# Out_conn.net
KiCad netlist of a schematic drawn in Altium Designer
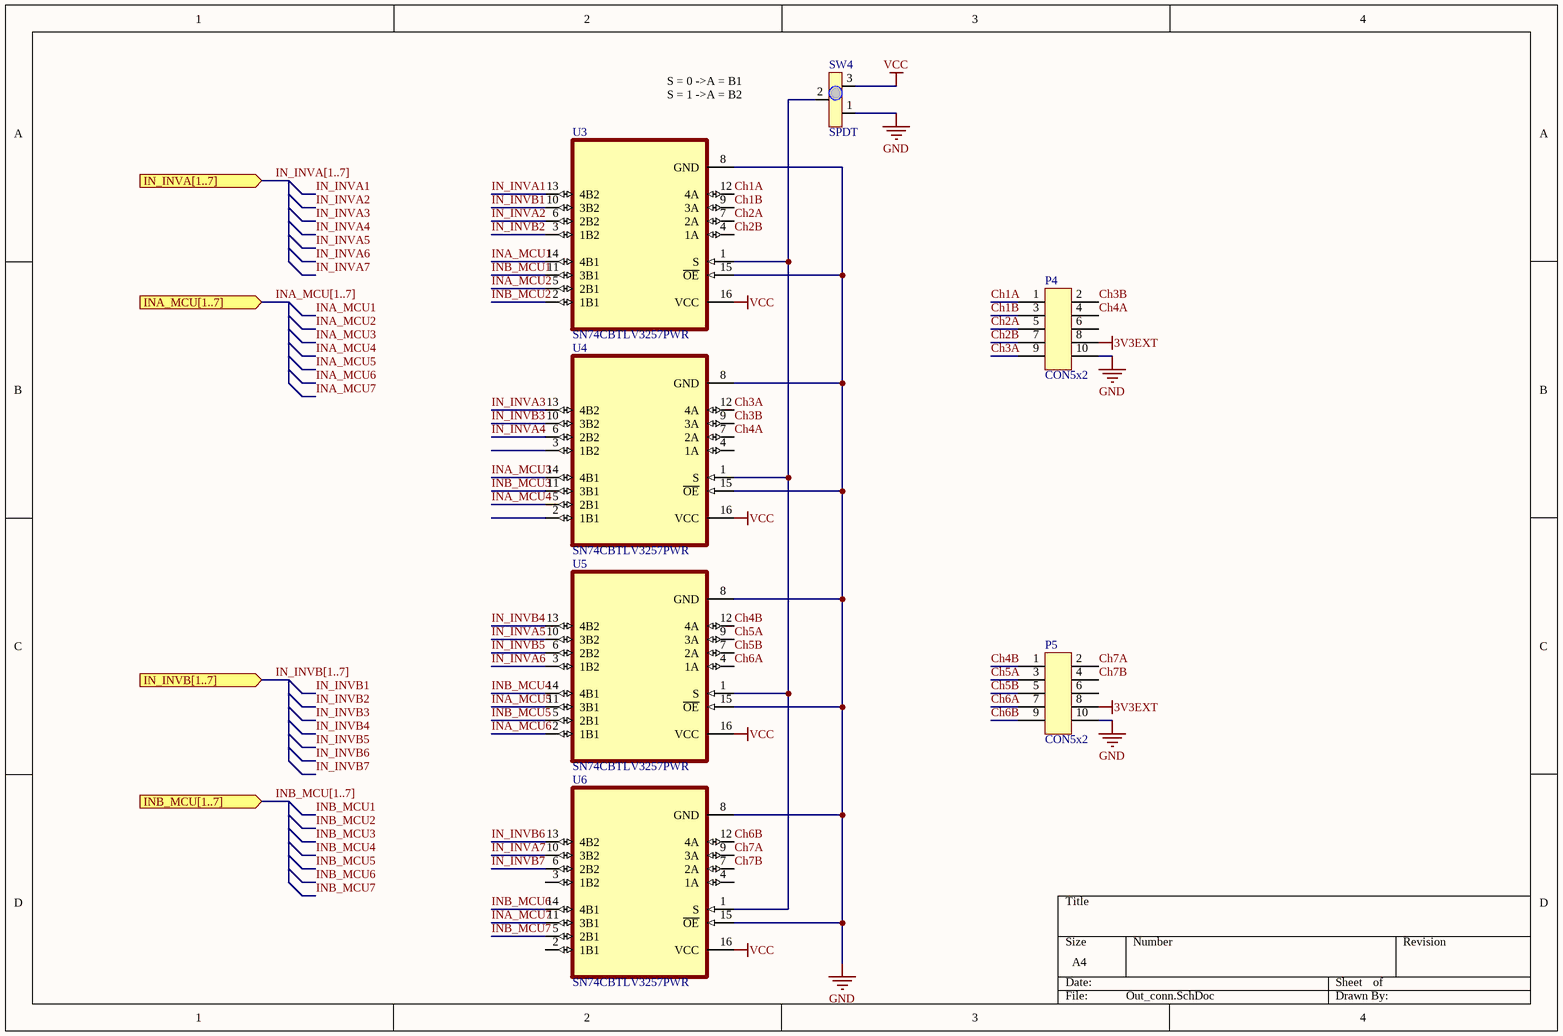
[diagram p0: Out_conn.SchDoc]

(export (version "E")
  (design (tool "Eeschema 10.0.6"))
  (components
    (comp (ref "P4")
      (value "CON5x2")
      (footprint "TBBTB2x5")
      (fields
        (field (name "DIGI-KEY PART NUMBER") "ED1543-ND")
        (field (name "MANUFACTURERS PART NUMBER") "302-S101")
      )
      (libsource (lib "PAT_Library") (part "PH_5x2"))
    )
    (comp (ref "P5")
      (value "CON5x2")
      (footprint "TBBTB2x5")
      (fields
        (field (name "DIGI-KEY PART NUMBER") "ED1543-ND")
        (field (name "MANUFACTURERS PART NUMBER") "302-S101")
      )
      (libsource (lib "PAT_Library") (part "PH_5x2"))
    )
    (comp (ref "SW4")
      (value "SPDT")
      (footprint "SPDT SMD")
      (description "200mA 12V")
      (fields
        (field (name "DIGI-KEY PART NUMBER") "563-1318-1-ND")
        (field (name "MANUFACTURERS PART NUMBER") "CL-SB-12B-01T")
      )
      (libsource (lib "PAT_Library") (part "SW_SPDT"))
    )
    (comp (ref "U3")
      (value "SN74CBTLV3257PWR")
      (footprint "SOP65P640X120-16N")
      (description "Multiplexer/Demultiplexer 4 x 1:2 16-TSSOP")
      (fields (field (name "DIGI-KEY PART NUMBER") "296-9138-1-ND"))
      (libsource (lib "SN74CBTLV3257PWR") (part "SN74CBTLV3257PWR"))
    )
    (comp (ref "U4")
      (value "SN74CBTLV3257PWR")
      (footprint "SOP65P640X120-16N")
      (description "Multiplexer/Demultiplexer 4 x 1:2 16-TSSOP")
      (fields (field (name "DIGI-KEY PART NUMBER") "296-9138-1-ND"))
      (libsource (lib "SN74CBTLV3257PWR") (part "SN74CBTLV3257PWR"))
    )
    (comp (ref "U5")
      (value "SN74CBTLV3257PWR")
      (footprint "SOP65P640X120-16N")
      (description "Multiplexer/Demultiplexer 4 x 1:2 16-TSSOP")
      (fields (field (name "DIGI-KEY PART NUMBER") "296-9138-1-ND"))
      (libsource (lib "SN74CBTLV3257PWR") (part "SN74CBTLV3257PWR"))
    )
    (comp (ref "U6")
      (value "SN74CBTLV3257PWR")
      (footprint "SOP65P640X120-16N")
      (description "Multiplexer/Demultiplexer 4 x 1:2 16-TSSOP")
      (fields (field (name "DIGI-KEY PART NUMBER") "296-9138-1-ND"))
      (libsource (lib "SN74CBTLV3257PWR") (part "SN74CBTLV3257PWR"))
    )
  )
  (nets
    (net (code "1") (name "/Ch1A") (class "Default")
      (node (ref "P4") (pin "1") (pintype "passive"))
      (node (ref "U3") (pin "12") (pinfunction "4A_12") (pintype "bidirectional"))
    )
    (net (code "2") (name "/Ch1B") (class "Default")
      (node (ref "P4") (pin "3") (pintype "passive"))
      (node (ref "U3") (pin "9") (pinfunction "3A_9") (pintype "bidirectional"))
    )
    (net (code "3") (name "/Ch2A") (class "Default")
      (node (ref "P4") (pin "5") (pintype "passive"))
      (node (ref "U3") (pin "7") (pinfunction "2A_7") (pintype "bidirectional"))
    )
    (net (code "4") (name "/Ch2B") (class "Default")
      (node (ref "P4") (pin "7") (pintype "passive"))
      (node (ref "U3") (pin "4") (pinfunction "1A_4") (pintype "bidirectional"))
    )
    (net (code "5") (name "/Ch3A") (class "Default")
      (node (ref "P4") (pin "9") (pintype "passive"))
      (node (ref "U4") (pin "12") (pinfunction "4A_12") (pintype "bidirectional"))
    )
    (net (code "6") (name "/Ch3B") (class "Default")
      (node (ref "P4") (pin "2") (pintype "passive"))
      (node (ref "U4") (pin "9") (pinfunction "3A_9") (pintype "bidirectional"))
    )
    (net (code "7") (name "/Ch4A") (class "Default")
      (node (ref "P4") (pin "4") (pintype "passive"))
      (node (ref "U4") (pin "7") (pinfunction "2A_7") (pintype "bidirectional"))
    )
    (net (code "8") (name "/Ch4B") (class "Default")
      (node (ref "P5") (pin "1") (pintype "passive"))
      (node (ref "U5") (pin "12") (pinfunction "4A_12") (pintype "bidirectional"))
    )
    (net (code "9") (name "/Ch5A") (class "Default")
      (node (ref "P5") (pin "3") (pintype "passive"))
      (node (ref "U5") (pin "9") (pinfunction "3A_9") (pintype "bidirectional"))
    )
    (net (code "10") (name "/Ch5B") (class "Default")
      (node (ref "P5") (pin "5") (pintype "passive"))
      (node (ref "U5") (pin "7") (pinfunction "2A_7") (pintype "bidirectional"))
    )
    (net (code "11") (name "/Ch6A") (class "Default")
      (node (ref "P5") (pin "7") (pintype "passive"))
      (node (ref "U5") (pin "4") (pinfunction "1A_4") (pintype "bidirectional"))
    )
    (net (code "12") (name "/Ch6B") (class "Default")
      (node (ref "P5") (pin "9") (pintype "passive"))
      (node (ref "U6") (pin "12") (pinfunction "4A_12") (pintype "bidirectional"))
    )
    (net (code "13") (name "/Ch7A") (class "Default")
      (node (ref "P5") (pin "2") (pintype "passive"))
      (node (ref "U6") (pin "9") (pinfunction "3A_9") (pintype "bidirectional"))
    )
    (net (code "14") (name "/Ch7B") (class "Default")
      (node (ref "P5") (pin "4") (pintype "passive"))
      (node (ref "U6") (pin "7") (pinfunction "2A_7") (pintype "bidirectional"))
    )
    (net (code "15") (name "/INA_MCU1") (class "Default")
      (node (ref "U3") (pin "14") (pinfunction "4B1_14") (pintype "bidirectional"))
    )
    (net (code "16") (name "/INA_MCU2") (class "Default")
      (node (ref "U3") (pin "5") (pinfunction "2B1_5") (pintype "bidirectional"))
    )
    (net (code "17") (name "/INA_MCU3") (class "Default")
      (node (ref "U4") (pin "14") (pinfunction "4B1_14") (pintype "bidirectional"))
    )
    (net (code "18") (name "/INA_MCU4") (class "Default")
      (node (ref "U4") (pin "5") (pinfunction "2B1_5") (pintype "bidirectional"))
    )
    (net (code "19") (name "/INA_MCU5") (class "Default")
      (node (ref "U5") (pin "11") (pinfunction "3B1_11") (pintype "bidirectional"))
    )
    (net (code "20") (name "/INA_MCU6") (class "Default")
      (node (ref "U5") (pin "2") (pinfunction "1B1_2") (pintype "bidirectional"))
    )
    (net (code "21") (name "/INA_MCU7") (class "Default")
      (node (ref "U6") (pin "11") (pinfunction "3B1_11") (pintype "bidirectional"))
    )
    (net (code "23") (name "/INB_MCU1") (class "Default")
      (node (ref "U3") (pin "11") (pinfunction "3B1_11") (pintype "bidirectional"))
    )
    (net (code "24") (name "/INB_MCU2") (class "Default")
      (node (ref "U3") (pin "2") (pinfunction "1B1_2") (pintype "bidirectional"))
    )
    (net (code "25") (name "/INB_MCU3") (class "Default")
      (node (ref "U4") (pin "11") (pinfunction "3B1_11") (pintype "bidirectional"))
    )
    (net (code "26") (name "/INB_MCU4") (class "Default")
      (node (ref "U5") (pin "14") (pinfunction "4B1_14") (pintype "bidirectional"))
    )
    (net (code "27") (name "/INB_MCU5") (class "Default")
      (node (ref "U5") (pin "5") (pinfunction "2B1_5") (pintype "bidirectional"))
    )
    (net (code "28") (name "/INB_MCU6") (class "Default")
      (node (ref "U6") (pin "14") (pinfunction "4B1_14") (pintype "bidirectional"))
    )
    (net (code "29") (name "/INB_MCU7") (class "Default")
      (node (ref "U6") (pin "5") (pinfunction "2B1_5") (pintype "bidirectional"))
    )
    (net (code "31") (name "/IN_INVA1") (class "Default")
      (node (ref "U3") (pin "13") (pinfunction "4B2_13") (pintype "bidirectional"))
    )
    (net (code "32") (name "/IN_INVA2") (class "Default")
      (node (ref "U3") (pin "6") (pinfunction "2B2_6") (pintype "bidirectional"))
    )
    (net (code "33") (name "/IN_INVA3") (class "Default")
      (node (ref "U4") (pin "13") (pinfunction "4B2_13") (pintype "bidirectional"))
    )
    (net (code "34") (name "/IN_INVA4") (class "Default")
      (node (ref "U4") (pin "6") (pinfunction "2B2_6") (pintype "bidirectional"))
    )
    (net (code "35") (name "/IN_INVA5") (class "Default")
      (node (ref "U5") (pin "10") (pinfunction "3B2_10") (pintype "bidirectional"))
    )
    (net (code "36") (name "/IN_INVA6") (class "Default")
      (node (ref "U5") (pin "3") (pinfunction "1B2_3") (pintype "bidirectional"))
    )
    (net (code "37") (name "/IN_INVA7") (class "Default")
      (node (ref "U6") (pin "10") (pinfunction "3B2_10") (pintype "bidirectional"))
    )
    (net (code "39") (name "/IN_INVB1") (class "Default")
      (node (ref "U3") (pin "10") (pinfunction "3B2_10") (pintype "bidirectional"))
    )
    (net (code "40") (name "/IN_INVB2") (class "Default")
      (node (ref "U3") (pin "3") (pinfunction "1B2_3") (pintype "bidirectional"))
    )
    (net (code "41") (name "/IN_INVB3") (class "Default")
      (node (ref "U4") (pin "10") (pinfunction "3B2_10") (pintype "bidirectional"))
    )
    (net (code "42") (name "/IN_INVB4") (class "Default")
      (node (ref "U5") (pin "13") (pinfunction "4B2_13") (pintype "bidirectional"))
    )
    (net (code "43") (name "/IN_INVB5") (class "Default")
      (node (ref "U5") (pin "6") (pinfunction "2B2_6") (pintype "bidirectional"))
    )
    (net (code "44") (name "/IN_INVB6") (class "Default")
      (node (ref "U6") (pin "13") (pinfunction "4B2_13") (pintype "bidirectional"))
    )
    (net (code "45") (name "/IN_INVB7") (class "Default")
      (node (ref "U6") (pin "6") (pinfunction "2B2_6") (pintype "bidirectional"))
    )
    (net (code "47") (name "3V3EXT") (class "Default")
      (node (ref "P4") (pin "8") (pintype "passive"))
      (node (ref "P5") (pin "8") (pintype "passive"))
    )
    (net (code "48") (name "GND") (class "Default")
      (node (ref "P4") (pin "10") (pintype "passive"))
      (node (ref "P5") (pin "10") (pintype "passive"))
      (node (ref "SW4") (pin "1") (pintype "passive"))
      (node (ref "U3") (pin "15") (pinfunction "~{OE}_15") (pintype "input"))
      (node (ref "U3") (pin "8") (pinfunction "GND_8") (pintype "passive"))
      (node (ref "U4") (pin "15") (pinfunction "~{OE}_15") (pintype "input"))
      (node (ref "U4") (pin "8") (pinfunction "GND_8") (pintype "passive"))
      (node (ref "U5") (pin "15") (pinfunction "~{OE}_15") (pintype "input"))
      (node (ref "U5") (pin "8") (pinfunction "GND_8") (pintype "passive"))
      (node (ref "U6") (pin "15") (pinfunction "~{OE}_15") (pintype "input"))
      (node (ref "U6") (pin "8") (pinfunction "GND_8") (pintype "passive"))
    )
    (net (code "49") (name "Net-(U3-S)") (class "Default")
      (node (ref "SW4") (pin "2") (pintype "passive"))
      (node (ref "U3") (pin "1") (pinfunction "S_1") (pintype "input"))
      (node (ref "U4") (pin "1") (pinfunction "S_1") (pintype "input"))
      (node (ref "U5") (pin "1") (pinfunction "S_1") (pintype "input"))
      (node (ref "U6") (pin "1") (pinfunction "S_1") (pintype "input"))
    )
    (net (code "50") (name "VCC") (class "Default")
      (node (ref "SW4") (pin "3") (pintype "passive"))
      (node (ref "U3") (pin "16") (pinfunction "VCC_16") (pintype "power_in"))
      (node (ref "U4") (pin "16") (pinfunction "VCC_16") (pintype "power_in"))
      (node (ref "U5") (pin "16") (pinfunction "VCC_16") (pintype "power_in"))
      (node (ref "U6") (pin "16") (pinfunction "VCC_16") (pintype "power_in"))
    )
    (net (code "51") (name "unconnected-(P4-Pad6)") (class "Default")
      (node (ref "P4") (pin "6") (pintype "passive"))
    )
    (net (code "52") (name "unconnected-(P5-Pad6)") (class "Default")
      (node (ref "P5") (pin "6") (pintype "passive"))
    )
    (net (code "53") (name "unconnected-(U4-1A-Pad4)") (class "Default")
      (node (ref "U4") (pin "4") (pinfunction "1A_4") (pintype "bidirectional"))
    )
    (net (code "54") (name "unconnected-(U4-1B1-Pad2)") (class "Default")
      (node (ref "U4") (pin "2") (pinfunction "1B1_2") (pintype "bidirectional"))
    )
    (net (code "55") (name "unconnected-(U4-1B2-Pad3)") (class "Default")
      (node (ref "U4") (pin "3") (pinfunction "1B2_3") (pintype "bidirectional"))
    )
    (net (code "56") (name "unconnected-(U6-1A-Pad4)") (class "Default")
      (node (ref "U6") (pin "4") (pinfunction "1A_4") (pintype "bidirectional"))
    )
    (net (code "57") (name "unconnected-(U6-1B1-Pad2)") (class "Default")
      (node (ref "U6") (pin "2") (pinfunction "1B1_2") (pintype "bidirectional"))
    )
    (net (code "58") (name "unconnected-(U6-1B2-Pad3)") (class "Default")
      (node (ref "U6") (pin "3") (pinfunction "1B2_3") (pintype "bidirectional"))
    )
  )
)
